# 02-BlockChart.net
KiCad netlist of a schematic drawn in Altium Designer
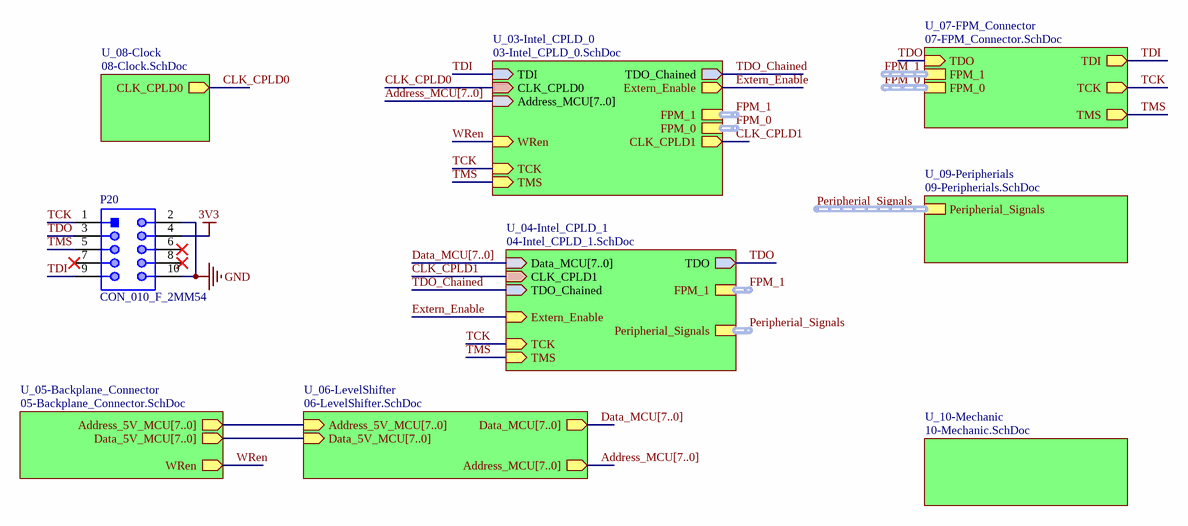
[diagram p0: 02-BlockChart.SchDoc]

(export (version "E")
  (design (tool "Eeschema 10.0.6"))
  (components
    (comp (ref "P20")
      (value "CON_010_F_2MM54")
      (footprint "CON_010_F_2MM54_Intel_Altera")
      (description "Male Box Header WR-BHD, THT, Vertical, pitch 2.54 mm, 10 pins")
      (libsource (lib "Schlib_EES") (part "CON_010_F_2MM54"))
    )
  )
  (nets
    (net (code "27") (name "/TCK") (class "Default")
      (node (ref "P20") (pin "1") (pinfunction "1_1") (pintype "passive"))
    )
    (net (code "28") (name "/TDI") (class "Default")
      (node (ref "P20") (pin "9") (pinfunction "9_9") (pintype "passive"))
    )
    (net (code "29") (name "/TDO") (class "Default")
      (node (ref "P20") (pin "3") (pinfunction "3_3") (pintype "passive"))
    )
    (net (code "31") (name "/TMS") (class "Default")
      (node (ref "P20") (pin "5") (pinfunction "5_5") (pintype "passive"))
    )
    (net (code "36") (name "3V3") (class "Default")
      (node (ref "P20") (pin "4") (pinfunction "4_4") (pintype "passive"))
    )
    (net (code "37") (name "GND") (class "Default")
      (node (ref "P20") (pin "10") (pinfunction "10_10") (pintype "passive"))
      (node (ref "P20") (pin "2") (pinfunction "2_2") (pintype "passive"))
    )
    (net (code "38") (name "unconnected-(P20-Pad6)") (class "Default")
      (node (ref "P20") (pin "6") (pinfunction "6_6") (pintype "passive+no_connect"))
    )
    (net (code "39") (name "unconnected-(P20-Pad7)") (class "Default")
      (node (ref "P20") (pin "7") (pinfunction "7_7") (pintype "passive+no_connect"))
    )
    (net (code "40") (name "unconnected-(P20-Pad8)") (class "Default")
      (node (ref "P20") (pin "8") (pinfunction "8_8") (pintype "passive+no_connect"))
    )
  )
)
